# isp.net
KiCad netlist of a schematic drawn in Altium Designer
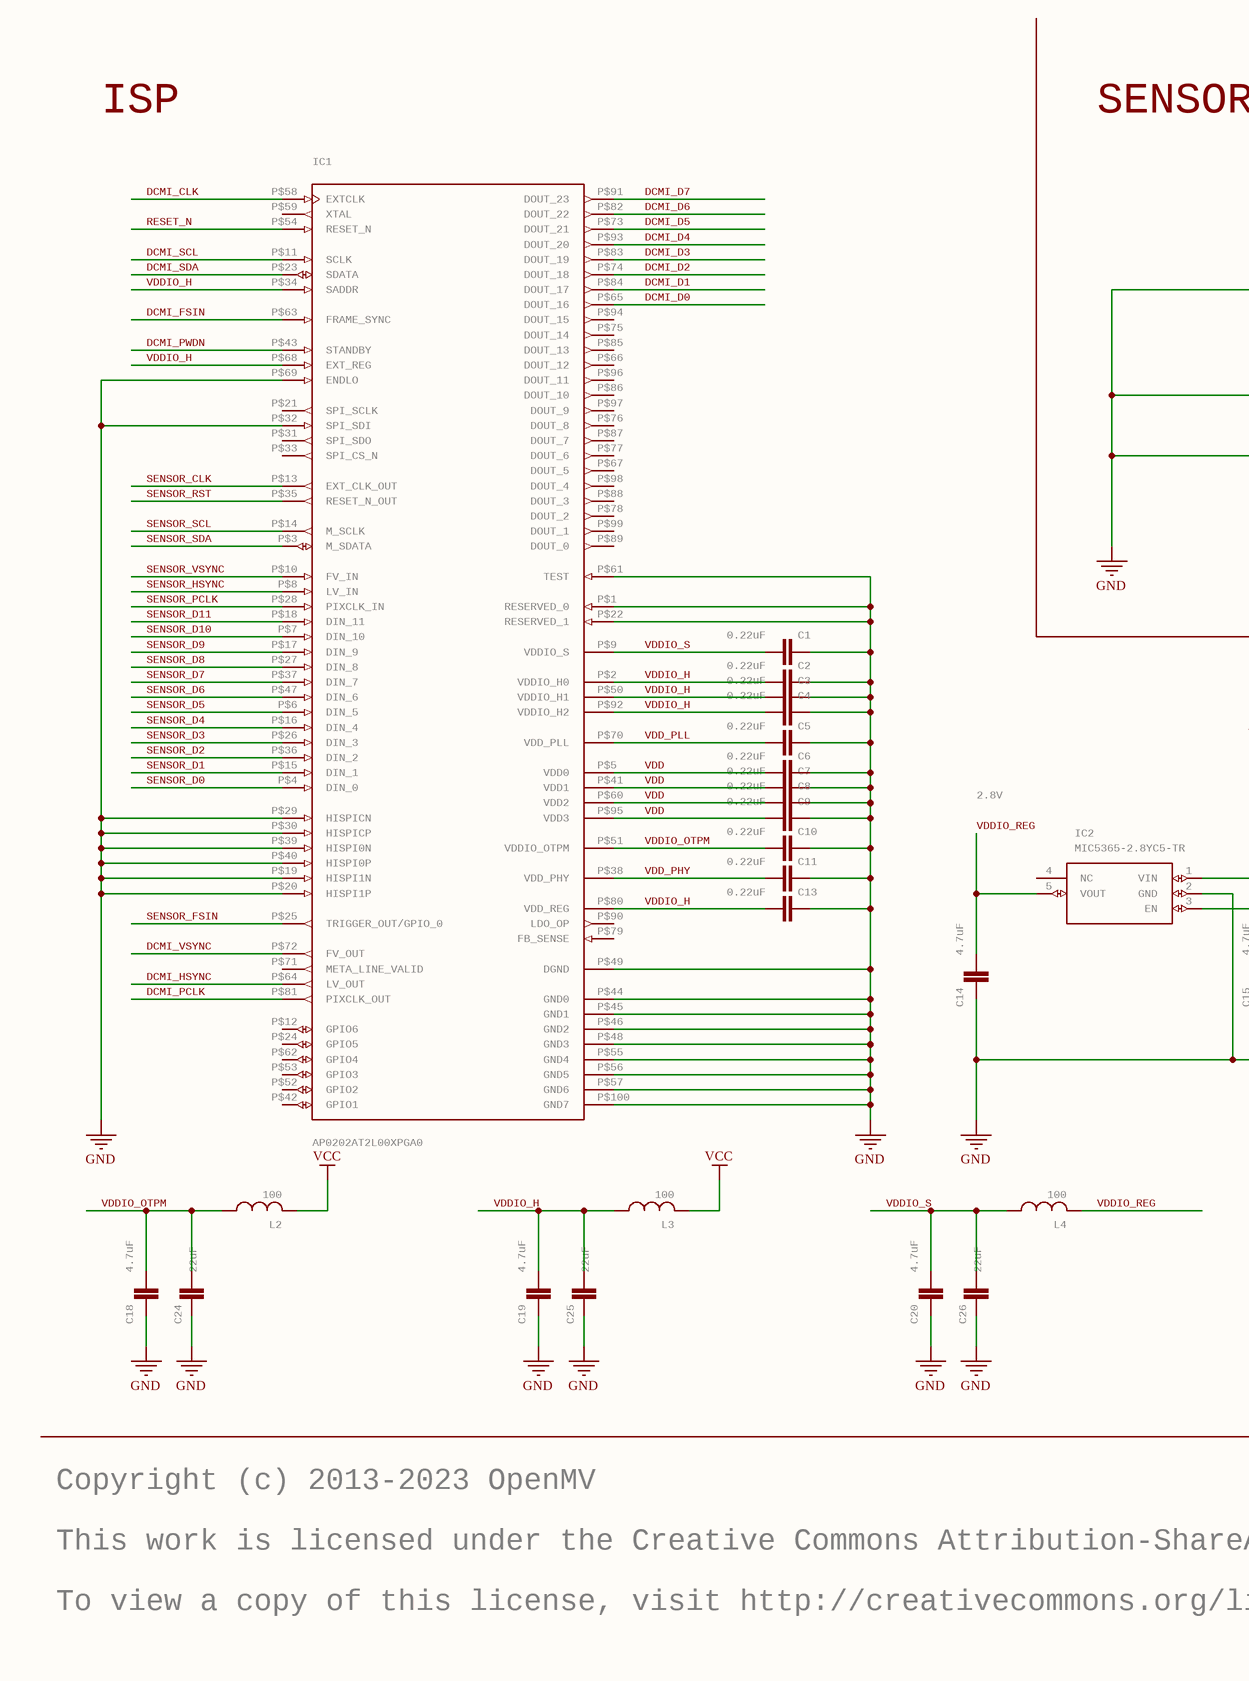
[diagram p0: isp.SchDoc, left]
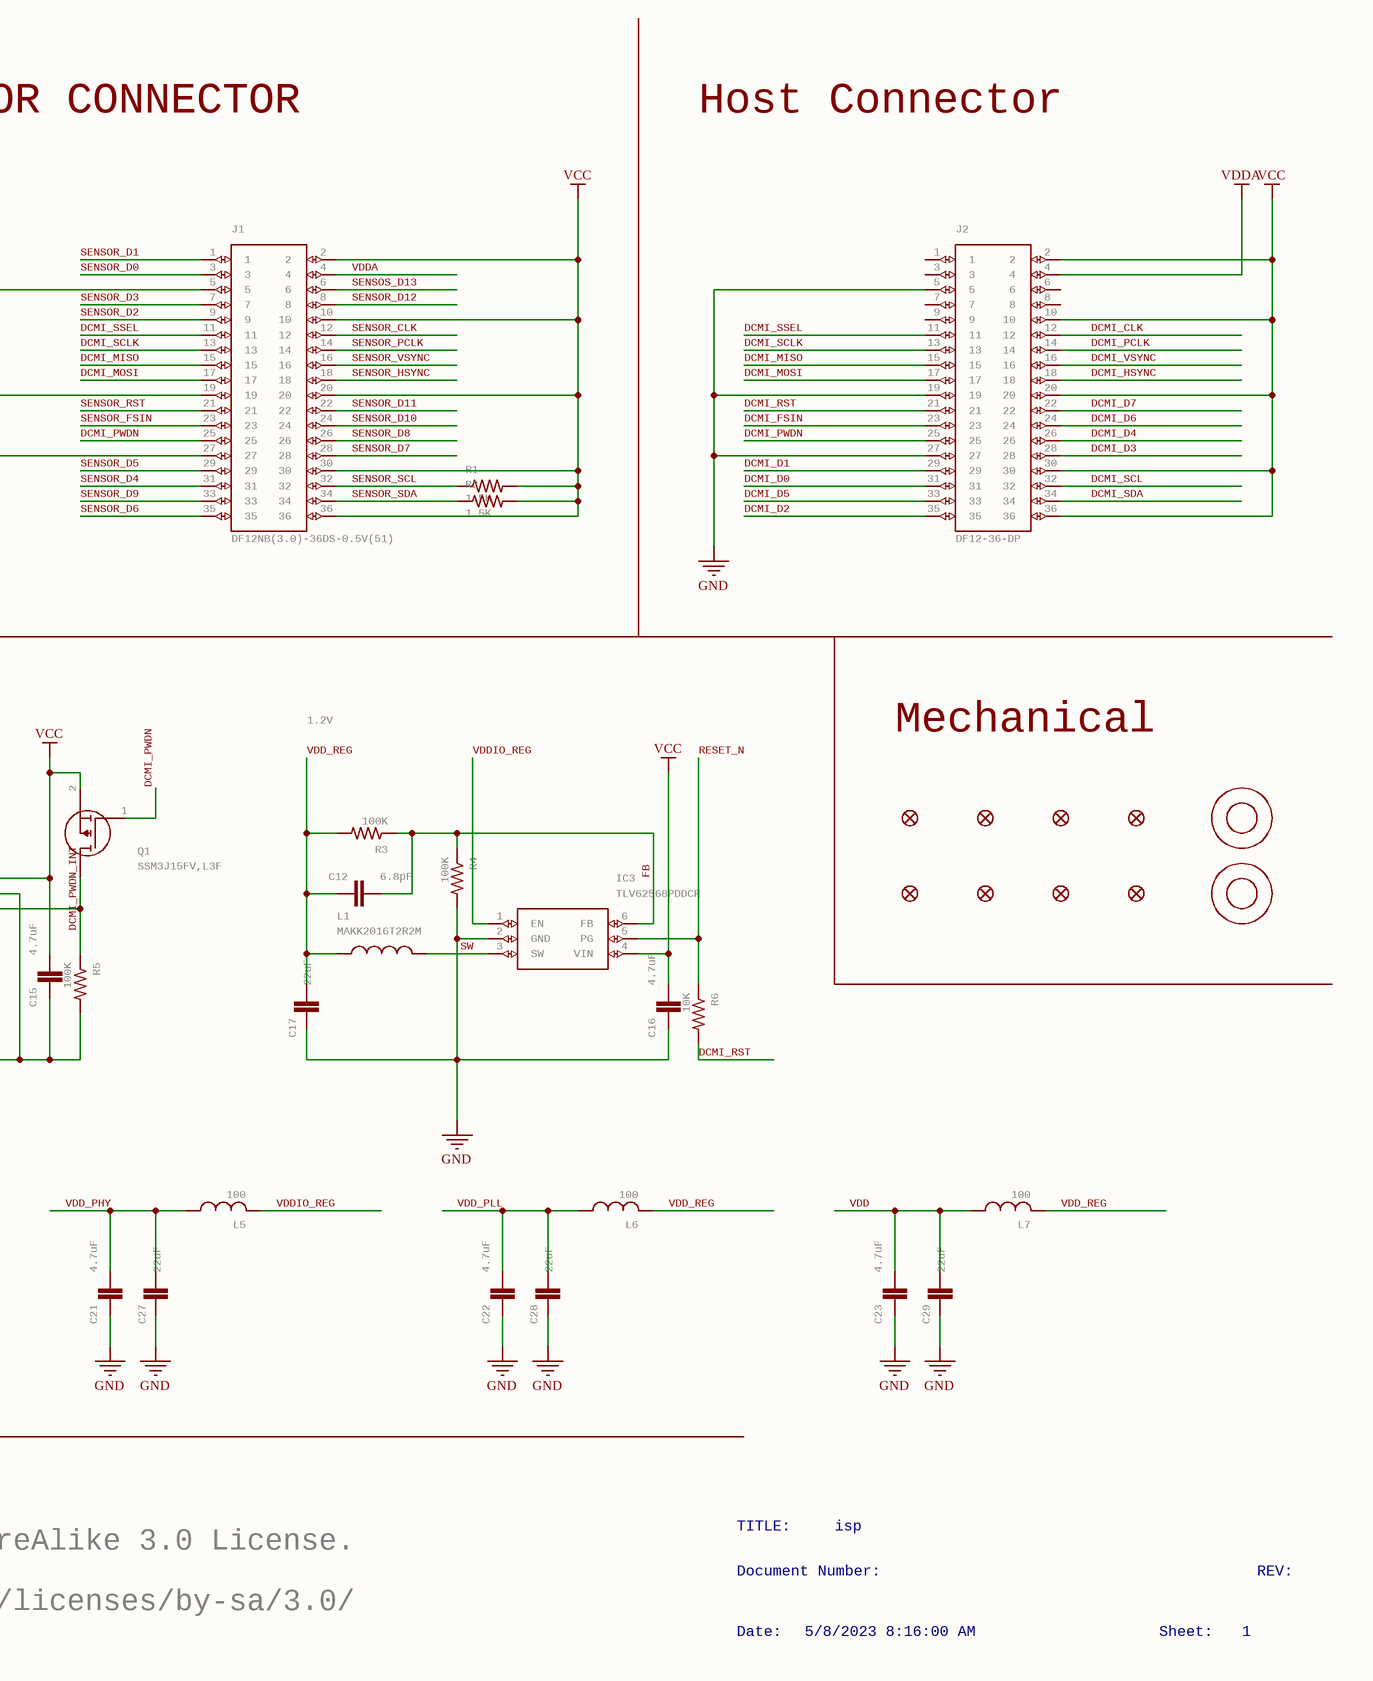
[diagram p1: isp.SchDoc, right]

(export (version "E")
  (design (tool "Eeschema 10.0.6"))
  (components
    (comp (ref "C1")
      (value "0.22uF")
      (footprint "C0201")
      (description "CAPACITOR, European symbol")
      (fields (field (name "MPN") "GRM033R60J224ME15D"))
      (libsource (lib "camera-modules") (part "C-EUC0201"))
    )
    (comp (ref "C2")
      (value "0.22uF")
      (footprint "C0201")
      (description "CAPACITOR, European symbol")
      (fields (field (name "MPN") "GRM033R60J224ME15D"))
      (libsource (lib "camera-modules") (part "C-EUC0201"))
    )
    (comp (ref "C3")
      (value "0.22uF")
      (footprint "C0201")
      (description "CAPACITOR, European symbol")
      (fields (field (name "MPN") "GRM033R60J224ME15D"))
      (libsource (lib "camera-modules") (part "C-EUC0201"))
    )
    (comp (ref "C4")
      (value "0.22uF")
      (footprint "C0201")
      (description "CAPACITOR, European symbol")
      (fields (field (name "MPN") "GRM033R60J224ME15D"))
      (libsource (lib "camera-modules") (part "C-EUC0201"))
    )
    (comp (ref "C5")
      (value "0.22uF")
      (footprint "C0201")
      (description "CAPACITOR, European symbol")
      (fields (field (name "MPN") "GRM033R60J224ME15D"))
      (libsource (lib "camera-modules") (part "C-EUC0201"))
    )
    (comp (ref "C6")
      (value "0.22uF")
      (footprint "C0201")
      (description "CAPACITOR, European symbol")
      (fields (field (name "MPN") "GRM033R60J224ME15D"))
      (libsource (lib "camera-modules") (part "C-EUC0201"))
    )
    (comp (ref "C7")
      (value "0.22uF")
      (footprint "C0201")
      (description "CAPACITOR, European symbol")
      (fields (field (name "MPN") "GRM033R60J224ME15D"))
      (libsource (lib "camera-modules") (part "C-EUC0201"))
    )
    (comp (ref "C8")
      (value "0.22uF")
      (footprint "C0201")
      (description "CAPACITOR, European symbol")
      (fields (field (name "MPN") "GRM033R60J224ME15D"))
      (libsource (lib "camera-modules") (part "C-EUC0201"))
    )
    (comp (ref "C9")
      (value "0.22uF")
      (footprint "C0201")
      (description "CAPACITOR, European symbol")
      (fields (field (name "MPN") "GRM033R60J224ME15D"))
      (libsource (lib "camera-modules") (part "C-EUC0201"))
    )
    (comp (ref "C10")
      (value "0.22uF")
      (footprint "C0201")
      (description "CAPACITOR, European symbol")
      (fields (field (name "MPN") "GRM033R60J224ME15D"))
      (libsource (lib "camera-modules") (part "C-EUC0201"))
    )
    (comp (ref "C11")
      (value "0.22uF")
      (footprint "C0201")
      (description "CAPACITOR, European symbol")
      (fields (field (name "MPN") "GRM033R60J224ME15D"))
      (libsource (lib "camera-modules") (part "C-EUC0201"))
    )
    (comp (ref "C12")
      (value "6.8pF")
      (footprint "0402")
      (description "0402 (1005 Metric) Nick Garner - TeleSense")
      (fields (field (name "MPN") "GRM1555C1H6R8DA01D"))
      (libsource (lib "") (part "CAP_0402_1"))
    )
    (comp (ref "C13")
      (value "0.22uF")
      (footprint "C0201")
      (description "CAPACITOR, European symbol")
      (fields (field (name "MPN") "GRM033R60J224ME15D"))
      (libsource (lib "camera-modules") (part "C-EUC0201"))
    )
    (comp (ref "C14")
      (value "4.7uF")
      (footprint "0402")
      (description "0402 (1005 Metric) Nick Garner - TeleSense")
      (fields (field (name "MPN") "JMK105BBJ475MV-F"))
      (libsource (lib "camera-modules") (part "CAP_0402"))
    )
    (comp (ref "C15")
      (value "4.7uF")
      (footprint "0402")
      (description "0402 (1005 Metric) Nick Garner - TeleSense")
      (fields (field (name "MPN") "JMK105BBJ475MV-F"))
      (libsource (lib "camera-modules") (part "CAP_0402"))
    )
    (comp (ref "C16")
      (value "4.7uF")
      (footprint "0402")
      (description "0402 (1005 Metric) Nick Garner - TeleSense")
      (fields (field (name "MPN") "JMK105BBJ475MV-F"))
      (libsource (lib "camera-modules") (part "CAP_0402"))
    )
    (comp (ref "C17")
      (value "22uF")
      (footprint "0805")
      (fields (field (name "MPN") "CL21A226MQQNNNE"))
      (libsource (lib "camera-modules") (part "22UF-0805-6.3V-20%"))
    )
    (comp (ref "C18")
      (value "4.7uF")
      (footprint "0402")
      (description "0402 (1005 Metric) Nick Garner - TeleSense")
      (fields (field (name "MPN") "JMK105BBJ475MV-F"))
      (libsource (lib "camera-modules") (part "CAP_0402"))
    )
    (comp (ref "C19")
      (value "4.7uF")
      (footprint "0402")
      (description "0402 (1005 Metric) Nick Garner - TeleSense")
      (fields (field (name "MPN") "JMK105BBJ475MV-F"))
      (libsource (lib "camera-modules") (part "CAP_0402"))
    )
    (comp (ref "C20")
      (value "4.7uF")
      (footprint "0402")
      (description "0402 (1005 Metric) Nick Garner - TeleSense")
      (fields (field (name "MPN") "JMK105BBJ475MV-F"))
      (libsource (lib "camera-modules") (part "CAP_0402"))
    )
    (comp (ref "C21")
      (value "4.7uF")
      (footprint "0402")
      (description "0402 (1005 Metric) Nick Garner - TeleSense")
      (fields (field (name "MPN") "JMK105BBJ475MV-F"))
      (libsource (lib "camera-modules") (part "CAP_0402"))
    )
    (comp (ref "C22")
      (value "4.7uF")
      (footprint "0402")
      (description "0402 (1005 Metric) Nick Garner - TeleSense")
      (fields (field (name "MPN") "JMK105BBJ475MV-F"))
      (libsource (lib "camera-modules") (part "CAP_0402"))
    )
    (comp (ref "C23")
      (value "4.7uF")
      (footprint "0402")
      (description "0402 (1005 Metric) Nick Garner - TeleSense")
      (fields (field (name "MPN") "JMK105BBJ475MV-F"))
      (libsource (lib "camera-modules") (part "CAP_0402"))
    )
    (comp (ref "C24")
      (value "22uF")
      (footprint "0805")
      (fields (field (name "MPN") "CL21A226MQQNNNE"))
      (libsource (lib "camera-modules") (part "22UF-0805-6.3V-20%"))
    )
    (comp (ref "C25")
      (value "22uF")
      (footprint "0805")
      (fields (field (name "MPN") "CL21A226MQQNNNE"))
      (libsource (lib "camera-modules") (part "22UF-0805-6.3V-20%"))
    )
    (comp (ref "C26")
      (value "22uF")
      (footprint "0805")
      (fields (field (name "MPN") "CL21A226MQQNNNE"))
      (libsource (lib "camera-modules") (part "22UF-0805-6.3V-20%"))
    )
    (comp (ref "C27")
      (value "22uF")
      (footprint "0805")
      (fields (field (name "MPN") "CL21A226MQQNNNE"))
      (libsource (lib "camera-modules") (part "22UF-0805-6.3V-20%"))
    )
    (comp (ref "C28")
      (value "22uF")
      (footprint "0805")
      (fields (field (name "MPN") "CL21A226MQQNNNE"))
      (libsource (lib "camera-modules") (part "22UF-0805-6.3V-20%"))
    )
    (comp (ref "C29")
      (value "22uF")
      (footprint "0805")
      (fields (field (name "MPN") "CL21A226MQQNNNE"))
      (libsource (lib "camera-modules") (part "22UF-0805-6.3V-20%"))
    )
    (comp (ref "FD1")
      (value "FIDUCIAL1X2")
      (footprint "FIDUCIAL-1X2")
      (fields (field (name "LIBRARYNAME") "SparkFun-Aesthetics"))
      (libsource (lib "camera-modules") (part "FIDUCIAL1X2"))
    )
    (comp (ref "FD2")
      (value "FIDUCIAL1X2")
      (footprint "FIDUCIAL-1X2")
      (fields (field (name "LIBRARYNAME") "SparkFun-Aesthetics"))
      (libsource (lib "camera-modules") (part "FIDUCIAL1X2"))
    )
    (comp (ref "FD3")
      (value "FIDUCIAL1X2")
      (footprint "FIDUCIAL-1X2")
      (fields (field (name "LIBRARYNAME") "SparkFun-Aesthetics"))
      (libsource (lib "camera-modules") (part "FIDUCIAL1X2"))
    )
    (comp (ref "FD4")
      (value "FIDUCIAL1X2")
      (footprint "FIDUCIAL-1X2")
      (fields (field (name "LIBRARYNAME") "SparkFun-Aesthetics"))
      (libsource (lib "camera-modules") (part "FIDUCIAL1X2"))
    )
    (comp (ref "FD5")
      (value "FIDUCIAL1X2")
      (footprint "FIDUCIAL-1X2")
      (fields (field (name "LIBRARYNAME") "SparkFun-Aesthetics"))
      (libsource (lib "camera-modules") (part "FIDUCIAL1X2"))
    )
    (comp (ref "FD6")
      (value "FIDUCIAL1X2")
      (footprint "FIDUCIAL-1X2")
      (fields (field (name "LIBRARYNAME") "SparkFun-Aesthetics"))
      (libsource (lib "camera-modules") (part "FIDUCIAL1X2"))
    )
    (comp (ref "FD7")
      (value "FIDUCIAL1X2")
      (footprint "FIDUCIAL-1X2")
      (fields (field (name "LIBRARYNAME") "SparkFun-Aesthetics"))
      (libsource (lib "camera-modules") (part "FIDUCIAL1X2"))
    )
    (comp (ref "FD8")
      (value "FIDUCIAL1X2")
      (footprint "FIDUCIAL-1X2")
      (fields (field (name "LIBRARYNAME") "SparkFun-Aesthetics"))
      (libsource (lib "camera-modules") (part "FIDUCIAL1X2"))
    )
    (comp (ref "IC1")
      (value "AP0202AT2L00XPGA0")
      (footprint "AP0202AT2L00XPGA0")
      (fields (field (name "MPN") "AP0202AT2L00XPGA0-DR"))
      (libsource (lib "camera-modules") (part "AP0202AT2L00XPGA0"))
    )
    (comp (ref "IC2")
      (value "MIC5365-2.8YC5-TR")
      (footprint "SOT65P210X110-5N")
      (description "IC REG LINEAR 2.8V 150MA SC70-5   Source:  Datasheet")
      (fields (field (name "MOUSER_PART_NUMBER") "998-MIC5365-2.8YC5TR"))
      (libsource (lib "camera-modules") (part "MIC5365-2.8YC5-TR"))
    )
    (comp (ref "IC3")
      (value "TLV62568PDDCR")
      (footprint "SOT95P280X110-6N")
      (fields (field (name "MOUSER_PART_NUMBER") "595-TLV62568PDDCR"))
      (libsource (lib "camera-modules") (part "TLV62568PDDCR"))
    )
    (comp (ref "J1")
      (value "DF12NB(3.0)-36DS-0.5V(51)")
      (footprint "DF12-36-DS")
      (libsource (lib "camera-modules") (part "DF12-36-DS"))
    )
    (comp (ref "J2")
      (value "DF12-36-DP")
      (footprint "DF12-36-DP")
      (fields (field (name "MPN") "DF12NB(3.0)-36DP-0.5V(51)"))
      (libsource (lib "camera-modules") (part "DF12-36-DP"))
    )
    (comp (ref "L1")
      (value "MAKK2016T2R2M")
      (footprint "INDC2016X100N")
      (description "INDUCTOR, METAL CORE Check availability")
      (fields (field (name "MF") "Taiyo Yuden"))
      (libsource (lib "camera-modules") (part "MAKK2016T2R2M"))
    )
    (comp (ref "L2")
      (value "100")
      (footprint "0402")
      (fields (field (name "MPN") "MFBM1V1005-101-R"))
      (libsource (lib "camera-modules") (part "INDUCTOR_0402"))
    )
    (comp (ref "L3")
      (value "100")
      (footprint "0402")
      (fields (field (name "MPN") "MFBM1V1005-101-R"))
      (libsource (lib "camera-modules") (part "INDUCTOR_0402"))
    )
    (comp (ref "L4")
      (value "100")
      (footprint "0402")
      (fields (field (name "MPN") "MFBM1V1005-101-R"))
      (libsource (lib "camera-modules") (part "INDUCTOR_0402"))
    )
    (comp (ref "L5")
      (value "100")
      (footprint "0402")
      (fields (field (name "MPN") "MFBM1V1005-101-R"))
      (libsource (lib "camera-modules") (part "INDUCTOR_0402"))
    )
    (comp (ref "L6")
      (value "100")
      (footprint "0402")
      (fields (field (name "MPN") "MFBM1V1005-101-R"))
      (libsource (lib "camera-modules") (part "INDUCTOR_0402"))
    )
    (comp (ref "L7")
      (value "100")
      (footprint "0402")
      (fields (field (name "MPN") "MFBM1V1005-101-R"))
      (libsource (lib "camera-modules") (part "INDUCTOR_0402"))
    )
    (comp (ref "M1")
      (value "9774030151R")
      (footprint "9774030243R")
      (libsource (lib "camera-modules") (part "9774030151R"))
    )
    (comp (ref "M2")
      (value "9774030151R")
      (footprint "9774030243R")
      (libsource (lib "camera-modules") (part "9774030151R"))
    )
    (comp (ref "Q1")
      (value "SSM3J15FV,L3F")
      (footprint "SSM3J15FV")
      (description "MOSFET 30 V, P-channel Trench MOSFET   Source:  Datasheet")
      (libsource (lib "camera-modules") (part "PMXB120EPEZ"))
    )
    (comp (ref "R1")
      (value "1.5K")
      (footprint "R0402")
      (description "RESISTOR, American symbol")
      (fields (field (name "MPN") "RC0402FR-131K5L"))
      (libsource (lib "camera-modules") (part "R-US_R0402"))
    )
    (comp (ref "R2")
      (value "1.5K")
      (footprint "R0402")
      (description "RESISTOR, American symbol")
      (fields (field (name "MPN") "RC0402FR-131K5L"))
      (libsource (lib "camera-modules") (part "R-US_R0402"))
    )
    (comp (ref "R3")
      (value "100K")
      (footprint "R0402")
      (description "RESISTOR, American symbol")
      (fields (field (name "MPN") "AC0402FR-07100KL"))
      (libsource (lib "camera-modules") (part "R-US_R0402"))
    )
    (comp (ref "R4")
      (value "100K")
      (footprint "R0402")
      (description "RESISTOR, American symbol")
      (fields (field (name "MPN") "AC0402FR-07100KL"))
      (libsource (lib "camera-modules") (part "R-US_R0402"))
    )
    (comp (ref "R5")
      (value "100K")
      (footprint "R0402")
      (description "RESISTOR, American symbol")
      (fields (field (name "MPN") "AC0402FR-07100KL"))
      (libsource (lib "camera-modules") (part "R-US_R0402"))
    )
    (comp (ref "R6")
      (value "10K")
      (footprint "R0402")
      (description "RESISTOR, American symbol")
      (fields (field (name "MPN") "AC0402FR-1310KL"))
      (libsource (lib "camera-modules") (part "R-US_R0402"))
    )
  )
  (nets
    (net (code "1") (name "/DCMI_CLK") (class "Default")
      (node (ref "IC1") (pin "P$58") (pinfunction "EXTCLK_P$58") (pintype "input"))
      (node (ref "J2") (pin "12") (pinfunction "12_12") (pintype "bidirectional"))
    )
    (net (code "2") (name "/DCMI_D0") (class "Default")
      (node (ref "IC1") (pin "P$65") (pinfunction "DOUT_16_P$65") (pintype "output"))
      (node (ref "J2") (pin "31") (pinfunction "31_31") (pintype "bidirectional"))
    )
    (net (code "3") (name "/DCMI_D1") (class "Default")
      (node (ref "IC1") (pin "P$84") (pinfunction "DOUT_17_P$84") (pintype "output"))
      (node (ref "J2") (pin "29") (pinfunction "29_29") (pintype "bidirectional"))
    )
    (net (code "4") (name "/DCMI_D2") (class "Default")
      (node (ref "IC1") (pin "P$74") (pinfunction "DOUT_18_P$74") (pintype "output"))
      (node (ref "J2") (pin "35") (pinfunction "35_35") (pintype "bidirectional"))
    )
    (net (code "5") (name "/DCMI_D3") (class "Default")
      (node (ref "IC1") (pin "P$83") (pinfunction "DOUT_19_P$83") (pintype "output"))
      (node (ref "J2") (pin "28") (pinfunction "28_28") (pintype "bidirectional"))
    )
    (net (code "6") (name "/DCMI_D4") (class "Default")
      (node (ref "IC1") (pin "P$93") (pinfunction "DOUT_20_P$93") (pintype "output"))
      (node (ref "J2") (pin "26") (pinfunction "26_26") (pintype "bidirectional"))
    )
    (net (code "7") (name "/DCMI_D5") (class "Default")
      (node (ref "IC1") (pin "P$73") (pinfunction "DOUT_21_P$73") (pintype "output"))
      (node (ref "J2") (pin "33") (pinfunction "33_33") (pintype "bidirectional"))
    )
    (net (code "8") (name "/DCMI_D6") (class "Default")
      (node (ref "IC1") (pin "P$82") (pinfunction "DOUT_22_P$82") (pintype "output"))
      (node (ref "J2") (pin "24") (pinfunction "24_24") (pintype "bidirectional"))
    )
    (net (code "9") (name "/DCMI_D7") (class "Default")
      (node (ref "IC1") (pin "P$91") (pinfunction "DOUT_23_P$91") (pintype "output"))
      (node (ref "J2") (pin "22") (pinfunction "22_22") (pintype "bidirectional"))
    )
    (net (code "10") (name "/DCMI_FSIN") (class "Default")
      (node (ref "IC1") (pin "P$63") (pinfunction "FRAME_SYNC_P$63") (pintype "input"))
      (node (ref "J2") (pin "23") (pinfunction "23_23") (pintype "bidirectional"))
    )
    (net (code "11") (name "/DCMI_HSYNC") (class "Default")
      (node (ref "IC1") (pin "P$64") (pinfunction "LV_OUT_P$64") (pintype "output"))
      (node (ref "J2") (pin "18") (pinfunction "18_18") (pintype "bidirectional"))
    )
    (net (code "12") (name "/DCMI_MISO") (class "Default")
      (node (ref "J1") (pin "15") (pinfunction "15_15") (pintype "bidirectional"))
      (node (ref "J2") (pin "15") (pinfunction "15_15") (pintype "bidirectional"))
    )
    (net (code "13") (name "/DCMI_MOSI") (class "Default")
      (node (ref "J1") (pin "17") (pinfunction "17_17") (pintype "bidirectional"))
      (node (ref "J2") (pin "17") (pinfunction "17_17") (pintype "bidirectional"))
    )
    (net (code "14") (name "/DCMI_PCLK") (class "Default")
      (node (ref "IC1") (pin "P$81") (pinfunction "PIXCLK_OUT_P$81") (pintype "output"))
      (node (ref "J2") (pin "14") (pinfunction "14_14") (pintype "bidirectional"))
    )
    (net (code "15") (name "/DCMI_PWDN") (class "Default")
      (node (ref "IC1") (pin "P$43") (pinfunction "STANDBY_P$43") (pintype "input"))
      (node (ref "J1") (pin "25") (pinfunction "25_25") (pintype "bidirectional"))
      (node (ref "J2") (pin "25") (pinfunction "25_25") (pintype "bidirectional"))
      (node (ref "Q1") (pin "1") (pinfunction "G_1") (pintype "bidirectional"))
    )
    (net (code "16") (name "/DCMI_PWDN_INT") (class "Default")
      (node (ref "IC2") (pin "3") (pinfunction "EN_3") (pintype "bidirectional"))
      (node (ref "Q1") (pin "3") (pinfunction "D_3") (pintype "bidirectional"))
      (node (ref "R5") (pin "1") (pinfunction "1_1") (pintype "passive"))
    )
    (net (code "17") (name "/DCMI_RST") (class "Default")
      (node (ref "J2") (pin "21") (pinfunction "21_21") (pintype "bidirectional"))
      (node (ref "R6") (pin "2") (pinfunction "2_2") (pintype "passive"))
    )
    (net (code "18") (name "/DCMI_SCL") (class "Default")
      (node (ref "IC1") (pin "P$11") (pinfunction "SCLK_P$11") (pintype "input"))
      (node (ref "J2") (pin "32") (pinfunction "32_32") (pintype "bidirectional"))
    )
    (net (code "19") (name "/DCMI_SCLK") (class "Default")
      (node (ref "J1") (pin "13") (pinfunction "13_13") (pintype "bidirectional"))
      (node (ref "J2") (pin "13") (pinfunction "13_13") (pintype "bidirectional"))
    )
    (net (code "20") (name "/DCMI_SDA") (class "Default")
      (node (ref "IC1") (pin "P$23") (pinfunction "SDATA_P$23") (pintype "bidirectional"))
      (node (ref "J2") (pin "34") (pinfunction "34_34") (pintype "bidirectional"))
    )
    (net (code "21") (name "/DCMI_SSEL") (class "Default")
      (node (ref "J1") (pin "11") (pinfunction "11_11") (pintype "bidirectional"))
      (node (ref "J2") (pin "11") (pinfunction "11_11") (pintype "bidirectional"))
    )
    (net (code "22") (name "/DCMI_VSYNC") (class "Default")
      (node (ref "IC1") (pin "P$72") (pinfunction "FV_OUT_P$72") (pintype "output"))
      (node (ref "J2") (pin "16") (pinfunction "16_16") (pintype "bidirectional"))
    )
    (net (code "23") (name "/FB") (class "Default")
      (node (ref "C12") (pin "2") (pinfunction "2_2") (pintype "passive"))
      (node (ref "IC3") (pin "6") (pinfunction "FB_6") (pintype "bidirectional"))
      (node (ref "R3") (pin "1") (pinfunction "1_1") (pintype "passive"))
      (node (ref "R4") (pin "1") (pinfunction "1_1") (pintype "passive"))
    )
    (net (code "24") (name "/RESET_N") (class "Default")
      (node (ref "IC1") (pin "P$54") (pinfunction "RESET_N_P$54") (pintype "input"))
      (node (ref "IC3") (pin "5") (pinfunction "PG_5") (pintype "bidirectional"))
      (node (ref "R6") (pin "1") (pinfunction "1_1") (pintype "passive"))
    )
    (net (code "25") (name "/SENSOR_CLK") (class "Default")
      (node (ref "IC1") (pin "P$13") (pinfunction "EXT_CLK_OUT_P$13") (pintype "output"))
      (node (ref "J1") (pin "12") (pinfunction "12_12") (pintype "bidirectional"))
    )
    (net (code "26") (name "/SENSOR_D0") (class "Default")
      (node (ref "IC1") (pin "P$4") (pinfunction "DIN_0_P$4") (pintype "input"))
      (node (ref "J1") (pin "3") (pinfunction "3_3") (pintype "bidirectional"))
    )
    (net (code "27") (name "/SENSOR_D1") (class "Default")
      (node (ref "IC1") (pin "P$15") (pinfunction "DIN_1_P$15") (pintype "input"))
      (node (ref "J1") (pin "1") (pinfunction "1_1") (pintype "bidirectional"))
    )
    (net (code "28") (name "/SENSOR_D2") (class "Default")
      (node (ref "IC1") (pin "P$36") (pinfunction "DIN_2_P$36") (pintype "input"))
      (node (ref "J1") (pin "9") (pinfunction "9_9") (pintype "bidirectional"))
    )
    (net (code "29") (name "/SENSOR_D3") (class "Default")
      (node (ref "IC1") (pin "P$26") (pinfunction "DIN_3_P$26") (pintype "input"))
      (node (ref "J1") (pin "7") (pinfunction "7_7") (pintype "bidirectional"))
    )
    (net (code "30") (name "/SENSOR_D4") (class "Default")
      (node (ref "IC1") (pin "P$16") (pinfunction "DIN_4_P$16") (pintype "input"))
      (node (ref "J1") (pin "31") (pinfunction "31_31") (pintype "bidirectional"))
    )
    (net (code "31") (name "/SENSOR_D5") (class "Default")
      (node (ref "IC1") (pin "P$6") (pinfunction "DIN_5_P$6") (pintype "input"))
      (node (ref "J1") (pin "29") (pinfunction "29_29") (pintype "bidirectional"))
    )
    (net (code "32") (name "/SENSOR_D6") (class "Default")
      (node (ref "IC1") (pin "P$47") (pinfunction "DIN_6_P$47") (pintype "input"))
      (node (ref "J1") (pin "35") (pinfunction "35_35") (pintype "bidirectional"))
    )
    (net (code "33") (name "/SENSOR_D7") (class "Default")
      (node (ref "IC1") (pin "P$37") (pinfunction "DIN_7_P$37") (pintype "input"))
      (node (ref "J1") (pin "28") (pinfunction "28_28") (pintype "bidirectional"))
    )
    (net (code "34") (name "/SENSOR_D8") (class "Default")
      (node (ref "IC1") (pin "P$27") (pinfunction "DIN_8_P$27") (pintype "input"))
      (node (ref "J1") (pin "26") (pinfunction "26_26") (pintype "bidirectional"))
    )
    (net (code "35") (name "/SENSOR_D9") (class "Default")
      (node (ref "IC1") (pin "P$17") (pinfunction "DIN_9_P$17") (pintype "input"))
      (node (ref "J1") (pin "33") (pinfunction "33_33") (pintype "bidirectional"))
    )
    (net (code "36") (name "/SENSOR_D10") (class "Default")
      (node (ref "IC1") (pin "P$7") (pinfunction "DIN_10_P$7") (pintype "input"))
      (node (ref "J1") (pin "24") (pinfunction "24_24") (pintype "bidirectional"))
    )
    (net (code "37") (name "/SENSOR_D11") (class "Default")
      (node (ref "IC1") (pin "P$18") (pinfunction "DIN_11_P$18") (pintype "input"))
      (node (ref "J1") (pin "22") (pinfunction "22_22") (pintype "bidirectional"))
    )
    (net (code "38") (name "/SENSOR_D12") (class "Default")
      (node (ref "J1") (pin "8") (pinfunction "8_8") (pintype "bidirectional"))
    )
    (net (code "39") (name "/SENSOR_FSIN") (class "Default")
      (node (ref "IC1") (pin "P$25") (pinfunction "TRIGGER_OUT/GPIO_0_P$25") (pintype "output"))
      (node (ref "J1") (pin "23") (pinfunction "23_23") (pintype "bidirectional"))
    )
    (net (code "40") (name "/SENSOR_HSYNC") (class "Default")
      (node (ref "IC1") (pin "P$8") (pinfunction "LV_IN_P$8") (pintype "input"))
      (node (ref "J1") (pin "18") (pinfunction "18_18") (pintype "bidirectional"))
    )
    (net (code "41") (name "/SENSOR_PCLK") (class "Default")
      (node (ref "IC1") (pin "P$28") (pinfunction "PIXCLK_IN_P$28") (pintype "input"))
      (node (ref "J1") (pin "14") (pinfunction "14_14") (pintype "bidirectional"))
    )
    (net (code "42") (name "/SENSOR_RST") (class "Default")
      (node (ref "IC1") (pin "P$35") (pinfunction "RESET_N_OUT_P$35") (pintype "output"))
      (node (ref "J1") (pin "21") (pinfunction "21_21") (pintype "bidirectional"))
    )
    (net (code "43") (name "/SENSOR_SCL") (class "Default")
      (node (ref "IC1") (pin "P$14") (pinfunction "M_SCLK_P$14") (pintype "output"))
      (node (ref "J1") (pin "32") (pinfunction "32_32") (pintype "bidirectional"))
      (node (ref "R1") (pin "1") (pinfunction "1_1") (pintype "passive"))
    )
    (net (code "44") (name "/SENSOR_SDA") (class "Default")
      (node (ref "IC1") (pin "P$3") (pinfunction "M_SDATA_P$3") (pintype "bidirectional"))
      (node (ref "J1") (pin "34") (pinfunction "34_34") (pintype "bidirectional"))
      (node (ref "R2") (pin "1") (pinfunction "1_1") (pintype "passive"))
    )
    (net (code "45") (name "/SENSOR_VSYNC") (class "Default")
      (node (ref "IC1") (pin "P$10") (pinfunction "FV_IN_P$10") (pintype "input"))
      (node (ref "J1") (pin "16") (pinfunction "16_16") (pintype "bidirectional"))
    )
    (net (code "46") (name "/SENSOS_D13") (class "Default")
      (node (ref "J1") (pin "6") (pinfunction "6_6") (pintype "bidirectional"))
    )
    (net (code "47") (name "/SW") (class "Default")
      (node (ref "IC3") (pin "3") (pinfunction "SW_3") (pintype "bidirectional"))
      (node (ref "L1") (pin "2") (pinfunction "2_2") (pintype "passive"))
    )
    (net (code "48") (name "/VDD") (class "Default")
      (node (ref "C23") (pin "2") (pinfunction "2_2") (pintype "passive"))
      (node (ref "C29") (pin "2") (pinfunction "2_2") (pintype "passive"))
      (node (ref "C6") (pin "2") (pinfunction "2_2") (pintype "passive"))
      (node (ref "C7") (pin "2") (pinfunction "2_2") (pintype "passive"))
      (node (ref "C8") (pin "2") (pinfunction "2_2") (pintype "passive"))
      (node (ref "C9") (pin "2") (pinfunction "2_2") (pintype "passive"))
      (node (ref "IC1") (pin "P$41") (pinfunction "VDD1_P$41") (pintype "power_in"))
      (node (ref "IC1") (pin "P$5") (pinfunction "VDD0_P$5") (pintype "power_in"))
      (node (ref "IC1") (pin "P$60") (pinfunction "VDD2_P$60") (pintype "power_in"))
      (node (ref "IC1") (pin "P$95") (pinfunction "VDD3_P$95") (pintype "power_in"))
      (node (ref "L7") (pin "1") (pinfunction "P$1_1") (pintype "passive"))
    )
    (net (code "49") (name "/VDDIO_H") (class "Default")
      (node (ref "C13") (pin "2") (pinfunction "2_2") (pintype "passive"))
      (node (ref "C19") (pin "2") (pinfunction "2_2") (pintype "passive"))
      (node (ref "C2") (pin "2") (pinfunction "2_2") (pintype "passive"))
      (node (ref "C25") (pin "2") (pinfunction "2_2") (pintype "passive"))
      (node (ref "C3") (pin "2") (pinfunction "2_2") (pintype "passive"))
      (node (ref "C4") (pin "2") (pinfunction "2_2") (pintype "passive"))
      (node (ref "IC1") (pin "P$2") (pinfunction "VDDIO_H0_P$2") (pintype "power_in"))
      (node (ref "IC1") (pin "P$34") (pinfunction "SADDR_P$34") (pintype "input"))
      (node (ref "IC1") (pin "P$50") (pinfunction "VDDIO_H1_P$50") (pintype "power_in"))
      (node (ref "IC1") (pin "P$68") (pinfunction "EXT_REG_P$68") (pintype "input"))
      (node (ref "IC1") (pin "P$80") (pinfunction "VDD_REG_P$80") (pintype "power_in"))
      (node (ref "IC1") (pin "P$92") (pinfunction "VDDIO_H2_P$92") (pintype "power_in"))
      (node (ref "L3") (pin "1") (pinfunction "P$1_1") (pintype "passive"))
    )
    (net (code "50") (name "/VDDIO_OTPM") (class "Default")
      (node (ref "C10") (pin "2") (pinfunction "2_2") (pintype "passive"))
      (node (ref "C18") (pin "2") (pinfunction "2_2") (pintype "passive"))
      (node (ref "C24") (pin "2") (pinfunction "2_2") (pintype "passive"))
      (node (ref "IC1") (pin "P$51") (pinfunction "VDDIO_OTPM_P$51") (pintype "power_in"))
      (node (ref "L2") (pin "1") (pinfunction "P$1_1") (pintype "passive"))
    )
    (net (code "51") (name "/VDDIO_REG") (class "Default")
      (node (ref "C14") (pin "2") (pinfunction "2_2") (pintype "passive"))
      (node (ref "IC2") (pin "5") (pinfunction "VOUT_5") (pintype "bidirectional"))
      (node (ref "IC3") (pin "1") (pinfunction "EN_1") (pintype "bidirectional"))
      (node (ref "L4") (pin "2") (pinfunction "P$2_2") (pintype "passive"))
      (node (ref "L5") (pin "2") (pinfunction "P$2_2") (pintype "passive"))
    )
    (net (code "52") (name "/VDDIO_S") (class "Default")
      (node (ref "C1") (pin "2") (pinfunction "2_2") (pintype "passive"))
      (node (ref "C20") (pin "2") (pinfunction "2_2") (pintype "passive"))
      (node (ref "C26") (pin "2") (pinfunction "2_2") (pintype "passive"))
      (node (ref "IC1") (pin "P$9") (pinfunction "VDDIO_S_P$9") (pintype "power_in"))
      (node (ref "L4") (pin "1") (pinfunction "P$1_1") (pintype "passive"))
    )
    (net (code "53") (name "/VDD_PHY") (class "Default")
      (node (ref "C11") (pin "2") (pinfunction "2_2") (pintype "passive"))
      (node (ref "C21") (pin "2") (pinfunction "2_2") (pintype "passive"))
      (node (ref "C27") (pin "2") (pinfunction "2_2") (pintype "passive"))
      (node (ref "IC1") (pin "P$38") (pinfunction "VDD_PHY_P$38") (pintype "power_in"))
      (node (ref "L5") (pin "1") (pinfunction "P$1_1") (pintype "passive"))
    )
    (net (code "54") (name "/VDD_PLL") (class "Default")
      (node (ref "C22") (pin "2") (pinfunction "2_2") (pintype "passive"))
      (node (ref "C28") (pin "2") (pinfunction "2_2") (pintype "passive"))
      (node (ref "C5") (pin "2") (pinfunction "2_2") (pintype "passive"))
      (node (ref "IC1") (pin "P$70") (pinfunction "VDD_PLL_P$70") (pintype "power_in"))
      (node (ref "L6") (pin "1") (pinfunction "P$1_1") (pintype "passive"))
    )
    (net (code "55") (name "/VDD_REG") (class "Default")
      (node (ref "C12") (pin "1") (pinfunction "1_1") (pintype "passive"))
      (node (ref "C17") (pin "2") (pinfunction "2_2") (pintype "passive"))
      (node (ref "L1") (pin "1") (pinfunction "1_1") (pintype "passive"))
      (node (ref "L6") (pin "2") (pinfunction "P$2_2") (pintype "passive"))
      (node (ref "L7") (pin "2") (pinfunction "P$2_2") (pintype "passive"))
      (node (ref "R3") (pin "2") (pinfunction "2_2") (pintype "passive"))
    )
    (net (code "56") (name "GND") (class "Default")
      (node (ref "C1") (pin "1") (pinfunction "1_1") (pintype "passive"))
      (node (ref "C10") (pin "1") (pinfunction "1_1") (pintype "passive"))
      (node (ref "C11") (pin "1") (pinfunction "1_1") (pintype "passive"))
      (node (ref "C13") (pin "1") (pinfunction "1_1") (pintype "passive"))
      (node (ref "C14") (pin "1") (pinfunction "1_1") (pintype "passive"))
      (node (ref "C15") (pin "1") (pinfunction "1_1") (pintype "passive"))
      (node (ref "C16") (pin "1") (pinfunction "1_1") (pintype "passive"))
      (node (ref "C17") (pin "1") (pinfunction "1_1") (pintype "passive"))
      (node (ref "C18") (pin "1") (pinfunction "1_1") (pintype "passive"))
      (node (ref "C19") (pin "1") (pinfunction "1_1") (pintype "passive"))
      (node (ref "C2") (pin "1") (pinfunction "1_1") (pintype "passive"))
      (node (ref "C20") (pin "1") (pinfunction "1_1") (pintype "passive"))
      (node (ref "C21") (pin "1") (pinfunction "1_1") (pintype "passive"))
      (node (ref "C22") (pin "1") (pinfunction "1_1") (pintype "passive"))
      (node (ref "C23") (pin "1") (pinfunction "1_1") (pintype "passive"))
      (node (ref "C24") (pin "1") (pinfunction "1_1") (pintype "passive"))
      (node (ref "C25") (pin "1") (pinfunction "1_1") (pintype "passive"))
      (node (ref "C26") (pin "1") (pinfunction "1_1") (pintype "passive"))
      (node (ref "C27") (pin "1") (pinfunction "1_1") (pintype "passive"))
      (node (ref "C28") (pin "1") (pinfunction "1_1") (pintype "passive"))
      (node (ref "C29") (pin "1") (pinfunction "1_1") (pintype "passive"))
      (node (ref "C3") (pin "1") (pinfunction "1_1") (pintype "passive"))
      (node (ref "C4") (pin "1") (pinfunction "1_1") (pintype "passive"))
      (node (ref "C5") (pin "1") (pinfunction "1_1") (pintype "passive"))
      (node (ref "C6") (pin "1") (pinfunction "1_1") (pintype "passive"))
      (node (ref "C7") (pin "1") (pinfunction "1_1") (pintype "passive"))
      (node (ref "C8") (pin "1") (pinfunction "1_1") (pintype "passive"))
      (node (ref "C9") (pin "1") (pinfunction "1_1") (pintype "passive"))
      (node (ref "IC1") (pin "P$1") (pinfunction "RESERVED_0_P$1") (pintype "input"))
      (node (ref "IC1") (pin "P$100") (pinfunction "GND7_P$100") (pintype "power_in"))
      (node (ref "IC1") (pin "P$19") (pinfunction "HISPI1N_P$19") (pintype "input"))
      (node (ref "IC1") (pin "P$20") (pinfunction "HISPI1P_P$20") (pintype "input"))
      (node (ref "IC1") (pin "P$22") (pinfunction "RESERVED_1_P$22") (pintype "input"))
      (node (ref "IC1") (pin "P$29") (pinfunction "HISPICN_P$29") (pintype "input"))
      (node (ref "IC1") (pin "P$30") (pinfunction "HISPICP_P$30") (pintype "input"))
      (node (ref "IC1") (pin "P$32") (pinfunction "SPI_SDI_P$32") (pintype "input"))
      (node (ref "IC1") (pin "P$39") (pinfunction "HISPI0N_P$39") (pintype "input"))
      (node (ref "IC1") (pin "P$40") (pinfunction "HISPI0P_P$40") (pintype "input"))
      (node (ref "IC1") (pin "P$44") (pinfunction "GND0_P$44") (pintype "power_in"))
      (node (ref "IC1") (pin "P$45") (pinfunction "GND1_P$45") (pintype "power_in"))
      (node (ref "IC1") (pin "P$46") (pinfunction "GND2_P$46") (pintype "power_in"))
      (node (ref "IC1") (pin "P$48") (pinfunction "GND3_P$48") (pintype "power_in"))
      (node (ref "IC1") (pin "P$49") (pinfunction "DGND_P$49") (pintype "power_in"))
      (node (ref "IC1") (pin "P$55") (pinfunction "GND4_P$55") (pintype "power_in"))
      (node (ref "IC1") (pin "P$56") (pinfunction "GND5_P$56") (pintype "power_in"))
      (node (ref "IC1") (pin "P$57") (pinfunction "GND6_P$57") (pintype "power_in"))
      (node (ref "IC1") (pin "P$61") (pinfunction "TEST_P$61") (pintype "input"))
      (node (ref "IC1") (pin "P$69") (pinfunction "ENDLO_P$69") (pintype "input"))
      (node (ref "IC2") (pin "2") (pinfunction "GND_2") (pintype "bidirectional"))
      (node (ref "IC3") (pin "2") (pinfunction "GND_2") (pintype "bidirectional"))
      (node (ref "J1") (pin "19") (pinfunction "19_19") (pintype "bidirectional"))
      (node (ref "J1") (pin "27") (pinfunction "27_27") (pintype "bidirectional"))
      (node (ref "J1") (pin "5") (pinfunction "5_5") (pintype "bidirectional"))
      (node (ref "J2") (pin "19") (pinfunction "19_19") (pintype "bidirectional"))
      (node (ref "J2") (pin "27") (pinfunction "27_27") (pintype "bidirectional"))
      (node (ref "J2") (pin "5") (pinfunction "5_5") (pintype "bidirectional"))
      (node (ref "R4") (pin "2") (pinfunction "2_2") (pintype "passive"))
      (node (ref "R5") (pin "2") (pinfunction "2_2") (pintype "passive"))
    )
    (net (code "57") (name "VCC") (class "Default")
      (node (ref "C15") (pin "2") (pinfunction "2_2") (pintype "passive"))
      (node (ref "C16") (pin "2") (pinfunction "2_2") (pintype "passive"))
      (node (ref "IC2") (pin "1") (pinfunction "VIN_1") (pintype "bidirectional"))
      (node (ref "IC3") (pin "4") (pinfunction "VIN_4") (pintype "bidirectional"))
      (node (ref "J1") (pin "10") (pinfunction "10_10") (pintype "bidirectional"))
      (node (ref "J1") (pin "2") (pinfunction "2_2") (pintype "bidirectional"))
      (node (ref "J1") (pin "20") (pinfunction "20_20") (pintype "bidirectional"))
      (node (ref "J1") (pin "30") (pinfunction "30_30") (pintype "bidirectional"))
      (node (ref "J1") (pin "36") (pinfunction "36_36") (pintype "bidirectional"))
      (node (ref "J2") (pin "10") (pinfunction "10_10") (pintype "bidirectional"))
      (node (ref "J2") (pin "2") (pinfunction "2_2") (pintype "bidirectional"))
      (node (ref "J2") (pin "20") (pinfunction "20_20") (pintype "bidirectional"))
      (node (ref "J2") (pin "30") (pinfunction "30_30") (pintype "bidirectional"))
      (node (ref "J2") (pin "36") (pinfunction "36_36") (pintype "bidirectional"))
      (node (ref "L2") (pin "2") (pinfunction "P$2_2") (pintype "passive"))
      (node (ref "L3") (pin "2") (pinfunction "P$2_2") (pintype "passive"))
      (node (ref "Q1") (pin "2") (pinfunction "S_2") (pintype "bidirectional"))
      (node (ref "R1") (pin "2") (pinfunction "2_2") (pintype "passive"))
      (node (ref "R2") (pin "2") (pinfunction "2_2") (pintype "passive"))
    )
    (net (code "58") (name "VDDA") (class "Default")
      (node (ref "J1") (pin "4") (pinfunction "4_4") (pintype "bidirectional"))
      (node (ref "J2") (pin "4") (pinfunction "4_4") (pintype "bidirectional"))
    )
    (net (code "59") (name "unconnected-(IC1-DOUT_0-PadP$89)") (class "Default")
      (node (ref "IC1") (pin "P$89") (pinfunction "DOUT_0_P$89") (pintype "output"))
    )
    (net (code "60") (name "unconnected-(IC1-DOUT_1-PadP$99)") (class "Default")
      (node (ref "IC1") (pin "P$99") (pinfunction "DOUT_1_P$99") (pintype "output"))
    )
    (net (code "61") (name "unconnected-(IC1-DOUT_2-PadP$78)") (class "Default")
      (node (ref "IC1") (pin "P$78") (pinfunction "DOUT_2_P$78") (pintype "output"))
    )
    (net (code "62") (name "unconnected-(IC1-DOUT_3-PadP$88)") (class "Default")
      (node (ref "IC1") (pin "P$88") (pinfunction "DOUT_3_P$88") (pintype "output"))
    )
    (net (code "63") (name "unconnected-(IC1-DOUT_4-PadP$98)") (class "Default")
      (node (ref "IC1") (pin "P$98") (pinfunction "DOUT_4_P$98") (pintype "output"))
    )
    (net (code "64") (name "unconnected-(IC1-DOUT_5-PadP$67)") (class "Default")
      (node (ref "IC1") (pin "P$67") (pinfunction "DOUT_5_P$67") (pintype "output"))
    )
    (net (code "65") (name "unconnected-(IC1-DOUT_6-PadP$77)") (class "Default")
      (node (ref "IC1") (pin "P$77") (pinfunction "DOUT_6_P$77") (pintype "output"))
    )
    (net (code "66") (name "unconnected-(IC1-DOUT_7-PadP$87)") (class "Default")
      (node (ref "IC1") (pin "P$87") (pinfunction "DOUT_7_P$87") (pintype "output"))
    )
    (net (code "67") (name "unconnected-(IC1-DOUT_8-PadP$76)") (class "Default")
      (node (ref "IC1") (pin "P$76") (pinfunction "DOUT_8_P$76") (pintype "output"))
    )
    (net (code "68") (name "unconnected-(IC1-DOUT_9-PadP$97)") (class "Default")
      (node (ref "IC1") (pin "P$97") (pinfunction "DOUT_9_P$97") (pintype "output"))
    )
    (net (code "69") (name "unconnected-(IC1-DOUT_10-PadP$86)") (class "Default")
      (node (ref "IC1") (pin "P$86") (pinfunction "DOUT_10_P$86") (pintype "output"))
    )
    (net (code "70") (name "unconnected-(IC1-DOUT_11-PadP$96)") (class "Default")
      (node (ref "IC1") (pin "P$96") (pinfunction "DOUT_11_P$96") (pintype "output"))
    )
    (net (code "71") (name "unconnected-(IC1-DOUT_12-PadP$66)") (class "Default")
      (node (ref "IC1") (pin "P$66") (pinfunction "DOUT_12_P$66") (pintype "output"))
    )
    (net (code "72") (name "unconnected-(IC1-DOUT_13-PadP$85)") (class "Default")
      (node (ref "IC1") (pin "P$85") (pinfunction "DOUT_13_P$85") (pintype "output"))
    )
    (net (code "73") (name "unconnected-(IC1-DOUT_14-PadP$75)") (class "Default")
      (node (ref "IC1") (pin "P$75") (pinfunction "DOUT_14_P$75") (pintype "output"))
    )
    (net (code "74") (name "unconnected-(IC1-DOUT_15-PadP$94)") (class "Default")
      (node (ref "IC1") (pin "P$94") (pinfunction "DOUT_15_P$94") (pintype "output"))
    )
    (net (code "75") (name "unconnected-(IC1-FB_SENSE-PadP$79)") (class "Default")
      (node (ref "IC1") (pin "P$79") (pinfunction "FB_SENSE_P$79") (pintype "input"))
    )
    (net (code "76") (name "unconnected-(IC1-GPIO1-PadP$42)") (class "Default")
      (node (ref "IC1") (pin "P$42") (pinfunction "GPIO1_P$42") (pintype "bidirectional"))
    )
    (net (code "77") (name "unconnected-(IC1-GPIO2-PadP$52)") (class "Default")
      (node (ref "IC1") (pin "P$52") (pinfunction "GPIO2_P$52") (pintype "bidirectional"))
    )
    (net (code "78") (name "unconnected-(IC1-GPIO3-PadP$53)") (class "Default")
      (node (ref "IC1") (pin "P$53") (pinfunction "GPIO3_P$53") (pintype "bidirectional"))
    )
    (net (code "79") (name "unconnected-(IC1-GPIO4-PadP$62)") (class "Default")
      (node (ref "IC1") (pin "P$62") (pinfunction "GPIO4_P$62") (pintype "bidirectional"))
    )
    (net (code "80") (name "unconnected-(IC1-GPIO5-PadP$24)") (class "Default")
      (node (ref "IC1") (pin "P$24") (pinfunction "GPIO5_P$24") (pintype "bidirectional"))
    )
    (net (code "81") (name "unconnected-(IC1-GPIO6-PadP$12)") (class "Default")
      (node (ref "IC1") (pin "P$12") (pinfunction "GPIO6_P$12") (pintype "bidirectional"))
    )
    (net (code "82") (name "unconnected-(IC1-LDO_OP-PadP$90)") (class "Default")
      (node (ref "IC1") (pin "P$90") (pinfunction "LDO_OP_P$90") (pintype "output"))
    )
    (net (code "83") (name "unconnected-(IC1-META_LINE_VALID-PadP$71)") (class "Default")
      (node (ref "IC1") (pin "P$71") (pinfunction "META_LINE_VALID_P$71") (pintype "output"))
    )
    (net (code "84") (name "unconnected-(IC1-SPI_CS_N-PadP$33)") (class "Default")
      (node (ref "IC1") (pin "P$33") (pinfunction "SPI_CS_N_P$33") (pintype "output"))
    )
    (net (code "85") (name "unconnected-(IC1-SPI_SCLK-PadP$21)") (class "Default")
      (node (ref "IC1") (pin "P$21") (pinfunction "SPI_SCLK_P$21") (pintype "output"))
    )
    (net (code "86") (name "unconnected-(IC1-SPI_SDO-PadP$31)") (class "Default")
      (node (ref "IC1") (pin "P$31") (pinfunction "SPI_SDO_P$31") (pintype "output"))
    )
    (net (code "87") (name "unconnected-(IC1-XTAL-PadP$59)") (class "Default")
      (node (ref "IC1") (pin "P$59") (pinfunction "XTAL_P$59") (pintype "output"))
    )
    (net (code "88") (name "unconnected-(IC2-NC-Pad4)") (class "Default")
      (node (ref "IC2") (pin "4") (pinfunction "NC_4") (pintype "passive"))
    )
    (net (code "89") (name "unconnected-(J2-Pad1)") (class "Default")
      (node (ref "J2") (pin "1") (pinfunction "1_1") (pintype "bidirectional"))
    )
    (net (code "90") (name "unconnected-(J2-Pad3)") (class "Default")
      (node (ref "J2") (pin "3") (pinfunction "3_3") (pintype "bidirectional"))
    )
    (net (code "91") (name "unconnected-(J2-Pad6)") (class "Default")
      (node (ref "J2") (pin "6") (pinfunction "6_6") (pintype "bidirectional"))
    )
    (net (code "92") (name "unconnected-(J2-Pad7)") (class "Default")
      (node (ref "J2") (pin "7") (pinfunction "7_7") (pintype "bidirectional"))
    )
    (net (code "93") (name "unconnected-(J2-Pad8)") (class "Default")
      (node (ref "J2") (pin "8") (pinfunction "8_8") (pintype "bidirectional"))
    )
    (net (code "94") (name "unconnected-(J2-Pad9)") (class "Default")
      (node (ref "J2") (pin "9") (pinfunction "9_9") (pintype "bidirectional"))
    )
  )
)
